# programmer.net
KiCad netlist of a schematic drawn in EAGLE
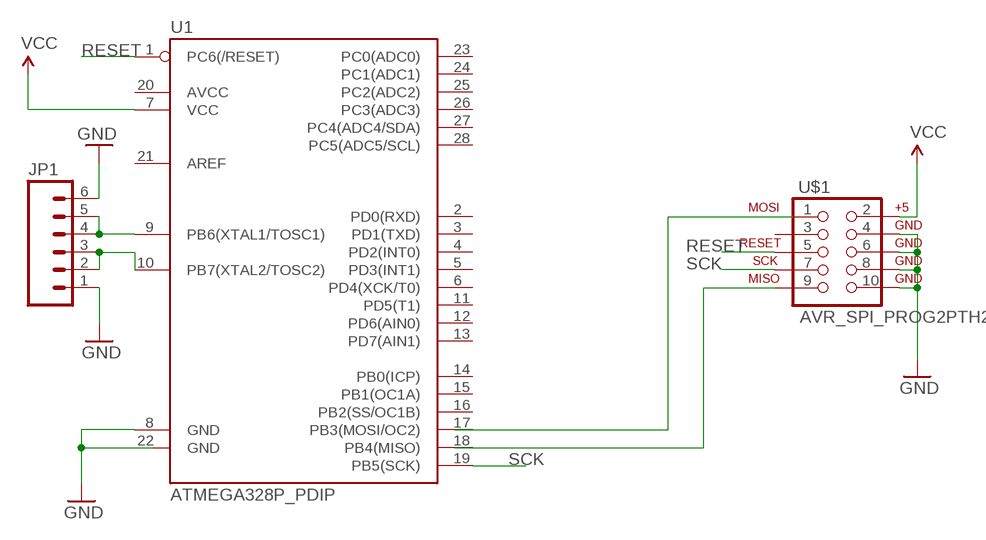
[diagram p0: schematic, sheet 1]

(export (version "E")
  (design (tool "Eeschema 10.0.6"))
  (components
    (comp (ref "JP1")
      (value "M06LOCK")
      (footprint "eagle-import:1X06_LOCK")
      (libsource (lib "eagle-import") (part "M06LOCK"))
    )
    (comp (ref "U$1")
      (value "AVR_SPI_PROG2PTH2")
      (footprint "eagle-import:2X5-SHROUDED")
      (libsource (lib "eagle-import") (part "AVR_SPI_PROG2PTH2"))
    )
    (comp (ref "U1")
      (value "ATMEGA328P_PDIP")
      (footprint "eagle-import:DIL28-3")
      (libsource (lib "eagle-import") (part "ATMEGA328P_PDIP"))
    )
  )
  (nets
    (net (code "1") (name "/RESET") (class "Default")
      (node (ref "U$1") (pin "5") (pinfunction "5_5") (pintype "passive"))
      (node (ref "U1") (pin "1") (pinfunction "PC6(/RESET)_1") (pintype "bidirectional"))
    )
    (net (code "2") (name "/SCK") (class "Default")
      (node (ref "U$1") (pin "7") (pinfunction "7_7") (pintype "passive"))
      (node (ref "U1") (pin "19") (pinfunction "PB5(SCK)_19") (pintype "bidirectional"))
    )
    (net (code "3") (name "GND") (class "Default")
      (node (ref "JP1") (pin "1") (pinfunction "1_1") (pintype "passive"))
      (node (ref "JP1") (pin "6") (pinfunction "6_6") (pintype "passive"))
      (node (ref "U$1") (pin "10") (pinfunction "10_10") (pintype "passive"))
      (node (ref "U$1") (pin "4") (pinfunction "4_4") (pintype "passive"))
      (node (ref "U$1") (pin "6") (pinfunction "6_6") (pintype "passive"))
      (node (ref "U$1") (pin "8") (pinfunction "8_8") (pintype "passive"))
      (node (ref "U1") (pin "8") (pinfunction "GND_8") (pintype "bidirectional"))
    )
    (net (code "4") (name "Net-(U1-PB6(XTAL1{slash}TOSC1))") (class "Default")
      (node (ref "JP1") (pin "4") (pinfunction "4_4") (pintype "passive"))
      (node (ref "JP1") (pin "5") (pinfunction "5_5") (pintype "passive"))
      (node (ref "U1") (pin "9") (pinfunction "PB6(XTAL1/TOSC1)_9") (pintype "bidirectional"))
    )
    (net (code "5") (name "Net-(U1-PB7(XTAL2{slash}TOSC2))") (class "Default")
      (node (ref "JP1") (pin "2") (pinfunction "2_2") (pintype "passive"))
      (node (ref "JP1") (pin "3") (pinfunction "3_3") (pintype "passive"))
      (node (ref "U1") (pin "10") (pinfunction "PB7(XTAL2/TOSC2)_10") (pintype "bidirectional"))
    )
    (net (code "6") (name "VCC") (class "Default")
      (node (ref "U$1") (pin "2") (pinfunction "2_2") (pintype "passive"))
      (node (ref "U1") (pin "7") (pinfunction "VCC_7") (pintype "bidirectional"))
    )
    (net (code "7") (name "unconnected-(U$1-Pad1)") (class "Default")
      (node (ref "U$1") (pin "1") (pinfunction "1_1") (pintype "passive"))
    )
    (net (code "8") (name "unconnected-(U$1-Pad3)") (class "Default")
      (node (ref "U$1") (pin "3") (pinfunction "3_3") (pintype "passive"))
    )
    (net (code "9") (name "unconnected-(U$1-Pad9)") (class "Default")
      (node (ref "U$1") (pin "9") (pinfunction "9_9") (pintype "passive"))
    )
    (net (code "10") (name "unconnected-(U1-AREF-Pad21)") (class "Default")
      (node (ref "U1") (pin "21") (pinfunction "AREF_21") (pintype "bidirectional"))
    )
    (net (code "11") (name "unconnected-(U1-AVCC-Pad20)") (class "Default")
      (node (ref "U1") (pin "20") (pinfunction "AVCC_20") (pintype "bidirectional"))
    )
    (net (code "12") (name "unconnected-(U1-GND-Pad22)") (class "Default")
      (node (ref "U1") (pin "22") (pinfunction "GND_22") (pintype "bidirectional"))
    )
    (net (code "13") (name "unconnected-(U1-PB0(ICP)-Pad14)") (class "Default")
      (node (ref "U1") (pin "14") (pinfunction "PB0(ICP)_14") (pintype "bidirectional"))
    )
    (net (code "14") (name "unconnected-(U1-PB1(OC1A)-Pad15)") (class "Default")
      (node (ref "U1") (pin "15") (pinfunction "PB1(OC1A)_15") (pintype "bidirectional"))
    )
    (net (code "15") (name "unconnected-(U1-PB2(SS{slash}OC1B)-Pad16)") (class "Default")
      (node (ref "U1") (pin "16") (pinfunction "PB2(SS/OC1B)_16") (pintype "bidirectional"))
    )
    (net (code "16") (name "unconnected-(U1-PB3(MOSI{slash}OC2)-Pad17)") (class "Default")
      (node (ref "U1") (pin "17") (pinfunction "PB3(MOSI/OC2)_17") (pintype "bidirectional"))
    )
    (net (code "17") (name "unconnected-(U1-PB4(MISO)-Pad18)") (class "Default")
      (node (ref "U1") (pin "18") (pinfunction "PB4(MISO)_18") (pintype "bidirectional"))
    )
    (net (code "18") (name "unconnected-(U1-PC0(ADC0)-Pad23)") (class "Default")
      (node (ref "U1") (pin "23") (pinfunction "PC0(ADC0)_23") (pintype "bidirectional"))
    )
    (net (code "19") (name "unconnected-(U1-PC1(ADC1)-Pad24)") (class "Default")
      (node (ref "U1") (pin "24") (pinfunction "PC1(ADC1)_24") (pintype "bidirectional"))
    )
    (net (code "20") (name "unconnected-(U1-PC2(ADC2)-Pad25)") (class "Default")
      (node (ref "U1") (pin "25") (pinfunction "PC2(ADC2)_25") (pintype "bidirectional"))
    )
    (net (code "21") (name "unconnected-(U1-PC3(ADC3)-Pad26)") (class "Default")
      (node (ref "U1") (pin "26") (pinfunction "PC3(ADC3)_26") (pintype "bidirectional"))
    )
    (net (code "22") (name "unconnected-(U1-PC4(ADC4{slash}SDA)-Pad27)") (class "Default")
      (node (ref "U1") (pin "27") (pinfunction "PC4(ADC4/SDA)_27") (pintype "bidirectional"))
    )
    (net (code "23") (name "unconnected-(U1-PC5(ADC5{slash}SCL)-Pad28)") (class "Default")
      (node (ref "U1") (pin "28") (pinfunction "PC5(ADC5/SCL)_28") (pintype "bidirectional"))
    )
    (net (code "24") (name "unconnected-(U1-PD0(RXD)-Pad2)") (class "Default")
      (node (ref "U1") (pin "2") (pinfunction "PD0(RXD)_2") (pintype "bidirectional"))
    )
    (net (code "25") (name "unconnected-(U1-PD1(TXD)-Pad3)") (class "Default")
      (node (ref "U1") (pin "3") (pinfunction "PD1(TXD)_3") (pintype "bidirectional"))
    )
    (net (code "26") (name "unconnected-(U1-PD2(INT0)-Pad4)") (class "Default")
      (node (ref "U1") (pin "4") (pinfunction "PD2(INT0)_4") (pintype "bidirectional"))
    )
    (net (code "27") (name "unconnected-(U1-PD3(INT1)-Pad5)") (class "Default")
      (node (ref "U1") (pin "5") (pinfunction "PD3(INT1)_5") (pintype "bidirectional"))
    )
    (net (code "28") (name "unconnected-(U1-PD4(XCK{slash}T0)-Pad6)") (class "Default")
      (node (ref "U1") (pin "6") (pinfunction "PD4(XCK/T0)_6") (pintype "bidirectional"))
    )
    (net (code "29") (name "unconnected-(U1-PD5(T1)-Pad11)") (class "Default")
      (node (ref "U1") (pin "11") (pinfunction "PD5(T1)_11") (pintype "bidirectional"))
    )
    (net (code "30") (name "unconnected-(U1-PD6(AIN0)-Pad12)") (class "Default")
      (node (ref "U1") (pin "12") (pinfunction "PD6(AIN0)_12") (pintype "bidirectional"))
    )
    (net (code "31") (name "unconnected-(U1-PD7(AIN1)-Pad13)") (class "Default")
      (node (ref "U1") (pin "13") (pinfunction "PD7(AIN1)_13") (pintype "bidirectional"))
    )
  )
)
